# PressureSwitch.net
KiCad netlist of a schematic drawn in Altium Designer
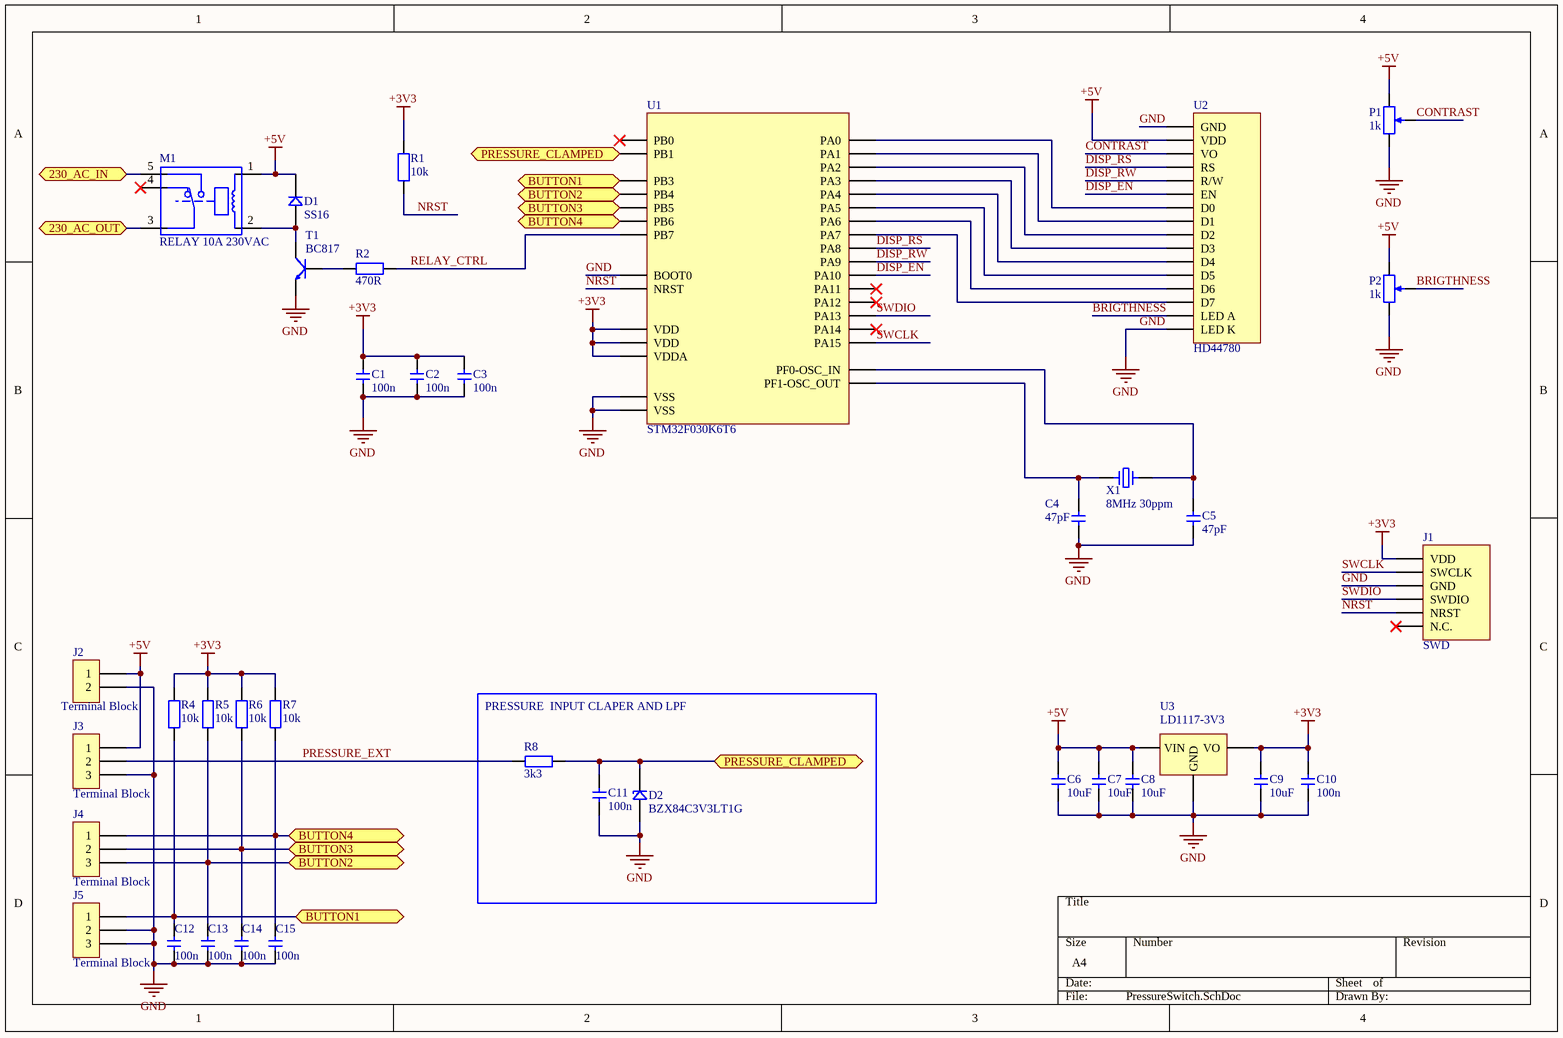
[diagram p0: PressureSwitch.SchDoc]

(export (version "E")
  (design (tool "Eeschema 10.0.6"))
  (components
    (comp (ref "C1")
      (value "100n")
      (footprint "CAP_1206")
      (description "1206  100n 50V Capacitor")
      (fields (field (name "TOLERANCE") "%") (field (name "VOLTAGE") "50V"))
      (libsource (lib "Passive") (part "100n 50V 1206"))
    )
    (comp (ref "C2")
      (value "100n")
      (footprint "CAP_1206")
      (description "1206  100n 50V Capacitor")
      (fields (field (name "TOLERANCE") "%") (field (name "VOLTAGE") "50V"))
      (libsource (lib "Passive") (part "100n 50V 1206"))
    )
    (comp (ref "C3")
      (value "100n")
      (footprint "CAP_1206")
      (description "1206  100n 50V Capacitor")
      (fields (field (name "TOLERANCE") "%") (field (name "VOLTAGE") "50V"))
      (libsource (lib "Passive") (part "100n 50V 1206"))
    )
    (comp (ref "C4")
      (value "47pF")
      (footprint "CAP_1206")
      (description "1206  47pF 50V Capacitor")
      (fields (field (name "TOLERANCE") "%") (field (name "VOLTAGE") "50V"))
      (libsource (lib "Passive") (part "47pF 50V 1206_1"))
    )
    (comp (ref "C5")
      (value "47pF")
      (footprint "CAP_1206")
      (description "1206  47pF 50V Capacitor")
      (fields (field (name "TOLERANCE") "%") (field (name "VOLTAGE") "50V"))
      (libsource (lib "Passive") (part "47pF 50V 1206_1"))
    )
    (comp (ref "C6")
      (value "10uF")
      (footprint "CAP_1206")
      (description "10uF 5% Capacitor")
      (fields (field (name "TOLERANCE") "%") (field (name "VOLTAGE") "V"))
      (libsource (lib "Passive") (part "10uF"))
    )
    (comp (ref "C7")
      (value "10uF")
      (footprint "CAP_1206")
      (description "10uF 5% Capacitor")
      (fields (field (name "TOLERANCE") "%") (field (name "VOLTAGE") "V"))
      (libsource (lib "Passive") (part "10uF"))
    )
    (comp (ref "C8")
      (value "10uF")
      (footprint "CAP_1206")
      (description "10uF 5% Capacitor")
      (fields (field (name "TOLERANCE") "%") (field (name "VOLTAGE") "V"))
      (libsource (lib "Passive") (part "10uF"))
    )
    (comp (ref "C9")
      (value "10uF")
      (footprint "CAP_1206")
      (description "10uF 5% Capacitor")
      (fields (field (name "TOLERANCE") "%") (field (name "VOLTAGE") "V"))
      (libsource (lib "Passive") (part "10uF"))
    )
    (comp (ref "C10")
      (value "100n")
      (footprint "CAP_1206")
      (description "1206  100n 50V Capacitor")
      (fields (field (name "TOLERANCE") "%") (field (name "VOLTAGE") "50V"))
      (libsource (lib "Passive") (part "100n 50V 1206"))
    )
    (comp (ref "C11")
      (value "100n")
      (footprint "CAP_1206")
      (description "1206  100n 50V Capacitor")
      (fields (field (name "TOLERANCE") "%") (field (name "VOLTAGE") "50V"))
      (libsource (lib "Passive") (part "100n 50V 1206"))
    )
    (comp (ref "C12")
      (value "100n")
      (footprint "CAP_1206")
      (description "1206  100n 50V Capacitor")
      (fields (field (name "TOLERANCE") "%") (field (name "VOLTAGE") "50V"))
      (libsource (lib "Passive") (part "100n 50V 1206"))
    )
    (comp (ref "C13")
      (value "100n")
      (footprint "CAP_1206")
      (description "1206  100n 50V Capacitor")
      (fields (field (name "TOLERANCE") "%") (field (name "VOLTAGE") "50V"))
      (libsource (lib "Passive") (part "100n 50V 1206"))
    )
    (comp (ref "C14")
      (value "100n")
      (footprint "CAP_1206")
      (description "1206  100n 50V Capacitor")
      (fields (field (name "TOLERANCE") "%") (field (name "VOLTAGE") "50V"))
      (libsource (lib "Passive") (part "100n 50V 1206"))
    )
    (comp (ref "C15")
      (value "100n")
      (footprint "CAP_1206")
      (description "1206  100n 50V Capacitor")
      (fields (field (name "TOLERANCE") "%") (field (name "VOLTAGE") "50V"))
      (libsource (lib "Passive") (part "100n 50V 1206"))
    )
    (comp (ref "D1")
      (value "SS16")
      (footprint "DO-214AC")
      (description "RECTIFIER 1A 60V")
      (libsource (lib "Discrete") (part "SS16"))
    )
    (comp (ref "D2")
      (value "BZX84C3V3LT1G")
      (footprint "SOT23-3")
      (description "3V3 ZENER DIODE 225 mW SOT−23")
      (libsource (lib "Discrete") (part "BZX84C3V3LT1G"))
    )
    (comp (ref "J1")
      (value "SWD")
      (footprint "PIN_HEADER_6P")
      (description "STM32 SWD CONNECTOR")
      (libsource (lib "Passive") (part "SWD"))
    )
    (comp (ref "J2")
      (value "Terminal Block")
      (footprint "TERMINAL_BLOCK_2P")
      (description "5.08mm Terminal Blocks 2P")
      (libsource (lib "Passive") (part "Terminal Block 2P"))
    )
    (comp (ref "J3")
      (value "Terminal Block")
      (footprint "TERMINAL_BLOCK_3P")
      (description "5.08mm Terminal Blocks 3P")
      (libsource (lib "Passive") (part "Terminal Block 3P"))
    )
    (comp (ref "J4")
      (value "Terminal Block")
      (footprint "TERMINAL_BLOCK_3P")
      (description "5.08mm Terminal Blocks 3P")
      (libsource (lib "Passive") (part "Terminal Block 3P"))
    )
    (comp (ref "J5")
      (value "Terminal Block")
      (footprint "TERMINAL_BLOCK_3P")
      (description "5.08mm Terminal Blocks 3P")
      (libsource (lib "Passive") (part "Terminal Block 3P"))
    )
    (comp (ref "M1")
      (value "RELAY 10A 230VAC")
      (footprint "Relay_10A")
      (description "MECH 5V 1xMORSE 10A/250AC S7001E5W 5DC")
      (libsource (lib "Passive") (part "RELAY 5V 10A/230VAC G6RN"))
    )
    (comp (ref "P1")
      (value "1k")
      (footprint "SMD_TRIM_POT")
      (description "Trimmer Pot 1k")
      (fields (field (name "TOLERANCE") "5%") (field (name "POWER") "W"))
      (libsource (lib "Passive") (part "1k_TRIMPOT"))
    )
    (comp (ref "P2")
      (value "1k")
      (footprint "SMD_TRIM_POT")
      (description "Trimmer Pot 1k")
      (fields (field (name "TOLERANCE") "5%") (field (name "POWER") "W"))
      (libsource (lib "Passive") (part "1k_TRIMPOT"))
    )
    (comp (ref "R1")
      (value "10k")
      (footprint "RES_1206")
      (description "1206 10k 5% Resistor")
      (fields (field (name "TOLERANCE") "5%") (field (name "POWER") "0.025W"))
      (libsource (lib "Passive") (part "10k"))
    )
    (comp (ref "R2")
      (value "470R")
      (footprint "RES_1206")
      (description "1206  470R 5% Resistor")
      (fields (field (name "TOLERANCE") "5%") (field (name "POWER") "W"))
      (libsource (lib "Passive") (part "470R"))
    )
    (comp (ref "R4")
      (value "10k")
      (footprint "RES_1206")
      (description "1206 10k 5% Resistor")
      (fields (field (name "TOLERANCE") "5%") (field (name "POWER") "0.025W"))
      (libsource (lib "Passive") (part "10k"))
    )
    (comp (ref "R5")
      (value "10k")
      (footprint "RES_1206")
      (description "1206 10k 5% Resistor")
      (fields (field (name "TOLERANCE") "5%") (field (name "POWER") "0.025W"))
      (libsource (lib "Passive") (part "10k"))
    )
    (comp (ref "R6")
      (value "10k")
      (footprint "RES_1206")
      (description "1206 10k 5% Resistor")
      (fields (field (name "TOLERANCE") "5%") (field (name "POWER") "0.025W"))
      (libsource (lib "Passive") (part "10k"))
    )
    (comp (ref "R7")
      (value "10k")
      (footprint "RES_1206")
      (description "1206 10k 5% Resistor")
      (fields (field (name "TOLERANCE") "5%") (field (name "POWER") "0.025W"))
      (libsource (lib "Passive") (part "10k"))
    )
    (comp (ref "R8")
      (value "3k3")
      (footprint "RES_1206")
      (description "1206  3k3 5% Resistor")
      (fields (field (name "TOLERANCE") "5%") (field (name "POWER") "W"))
      (libsource (lib "Passive") (part "3k3"))
    )
    (comp (ref "T1")
      (value "BC817")
      (footprint "SOT23-3")
      (description "BC817 NPN-UNI 45V 0.5A 0.25W 200MHz SOT-23")
      (fields (field (name "POWER") "0.25W"))
      (libsource (lib "Discrete") (part "BC817"))
    )
    (comp (ref "U1")
      (value "STM32F030K6T6")
      (footprint "LQFP32")
      (description "Value-line ARM 32bit MCU with 32k Flash")
      (libsource (lib "IC") (part "STM32F030K6T6"))
    )
    (comp (ref "U2")
      (value "HD44780")
      (footprint "SOCKET_HEADER_16P")
      (description "16x2 CHARACTER DISPLAY")
      (libsource (lib "IC") (part "HD44780"))
    )
    (comp (ref "U3")
      (value "LD1117-3V3")
      (footprint "SOT223-3")
      (description "3.3V low drop positive voltage regulator")
      (libsource (lib "IC") (part "LD1117-3V3"))
    )
    (comp (ref "X1")
      (value "8MHz 30ppm")
      (footprint "HC49")
      (description "8.000MHz QUARZ HC49 30ppm 20pF LOW PROFILE")
      (libsource (lib "Passive") (part "XTAL_8MHZ"))
    )
  )
  (nets
    (net (code "1") (name "+3V3") (class "Default")
      (node (ref "C1") (pin "2") (pinfunction "2_2") (pintype "passive"))
      (node (ref "C10") (pin "2") (pinfunction "2_2") (pintype "passive"))
      (node (ref "C2") (pin "2") (pinfunction "2_2") (pintype "passive"))
      (node (ref "C3") (pin "2") (pinfunction "2_2") (pintype "passive"))
      (node (ref "C9") (pin "2") (pinfunction "2_2") (pintype "passive"))
      (node (ref "J1") (pin "1") (pinfunction "VDD_1") (pintype "passive"))
      (node (ref "R1") (pin "2") (pinfunction "2_2") (pintype "passive"))
      (node (ref "R4") (pin "2") (pinfunction "2_2") (pintype "passive"))
      (node (ref "R5") (pin "2") (pinfunction "2_2") (pintype "passive"))
      (node (ref "R6") (pin "2") (pinfunction "2_2") (pintype "passive"))
      (node (ref "R7") (pin "2") (pinfunction "2_2") (pintype "passive"))
      (node (ref "U1") (pin "1") (pinfunction "VDD_1") (pintype "passive"))
      (node (ref "U1") (pin "17") (pinfunction "VDD_17") (pintype "passive"))
      (node (ref "U1") (pin "5") (pinfunction "VDDA_5") (pintype "passive"))
      (node (ref "U3") (pin "2") (pinfunction "VO_2") (pintype "passive"))
    )
    (net (code "2") (name "+5V") (class "Default")
      (node (ref "C6") (pin "2") (pinfunction "2_2") (pintype "passive"))
      (node (ref "C7") (pin "2") (pinfunction "2_2") (pintype "passive"))
      (node (ref "C8") (pin "2") (pinfunction "2_2") (pintype "passive"))
      (node (ref "D1") (pin "2") (pinfunction "2_2") (pintype "passive"))
      (node (ref "J2") (pin "1") (pinfunction "1_1") (pintype "passive"))
      (node (ref "J3") (pin "1") (pinfunction "1_1") (pintype "passive"))
      (node (ref "M1") (pin "1") (pinfunction "1_1") (pintype "passive"))
      (node (ref "P1") (pin "1") (pinfunction "1_1") (pintype "passive"))
      (node (ref "P2") (pin "1") (pinfunction "1_1") (pintype "passive"))
      (node (ref "U2") (pin "2") (pinfunction "VDD_2") (pintype "passive"))
      (node (ref "U3") (pin "3") (pinfunction "VIN_3") (pintype "passive"))
    )
    (net (code "3") (name "/230_AC_IN") (class "Default")
      (node (ref "M1") (pin "5") (pinfunction "5_5") (pintype "passive"))
    )
    (net (code "4") (name "/230_AC_OUT") (class "Default")
      (node (ref "M1") (pin "3") (pinfunction "3_3") (pintype "passive"))
    )
    (net (code "5") (name "/BRIGTHNESS") (class "Default")
      (node (ref "P2") (pin "3") (pinfunction "3_3") (pintype "passive"))
      (node (ref "U2") (pin "15") (pinfunction "LED_A_15") (pintype "passive"))
    )
    (net (code "6") (name "/BUTTON1") (class "Default")
      (node (ref "C12") (pin "2") (pinfunction "2_2") (pintype "passive"))
      (node (ref "J5") (pin "1") (pinfunction "1_1") (pintype "passive"))
      (node (ref "R4") (pin "1") (pinfunction "1_1") (pintype "passive"))
      (node (ref "U1") (pin "26") (pinfunction "PB3_26") (pintype "passive"))
    )
    (net (code "7") (name "/BUTTON2") (class "Default")
      (node (ref "C13") (pin "2") (pinfunction "2_2") (pintype "passive"))
      (node (ref "J4") (pin "3") (pinfunction "3_3") (pintype "passive"))
      (node (ref "R5") (pin "1") (pinfunction "1_1") (pintype "passive"))
      (node (ref "U1") (pin "27") (pinfunction "PB4_27") (pintype "passive"))
    )
    (net (code "8") (name "/BUTTON3") (class "Default")
      (node (ref "C14") (pin "2") (pinfunction "2_2") (pintype "passive"))
      (node (ref "J4") (pin "2") (pinfunction "2_2") (pintype "passive"))
      (node (ref "R6") (pin "1") (pinfunction "1_1") (pintype "passive"))
      (node (ref "U1") (pin "28") (pinfunction "PB5_28") (pintype "passive"))
    )
    (net (code "9") (name "/BUTTON4") (class "Default")
      (node (ref "C15") (pin "2") (pinfunction "2_2") (pintype "passive"))
      (node (ref "J4") (pin "1") (pinfunction "1_1") (pintype "passive"))
      (node (ref "R7") (pin "1") (pinfunction "1_1") (pintype "passive"))
      (node (ref "U1") (pin "29") (pinfunction "PB6_29") (pintype "passive"))
    )
    (net (code "10") (name "/CONTRAST") (class "Default")
      (node (ref "P1") (pin "3") (pinfunction "3_3") (pintype "passive"))
      (node (ref "U2") (pin "3") (pinfunction "VO_3") (pintype "passive"))
    )
    (net (code "11") (name "/DISP_EN") (class "Default")
      (node (ref "U1") (pin "20") (pinfunction "PA10_20") (pintype "passive"))
      (node (ref "U2") (pin "6") (pinfunction "EN_6") (pintype "passive"))
    )
    (net (code "12") (name "/DISP_RS") (class "Default")
      (node (ref "U1") (pin "18") (pinfunction "PA8_18") (pintype "passive"))
      (node (ref "U2") (pin "4") (pinfunction "RS_4") (pintype "passive"))
    )
    (net (code "13") (name "/DISP_RW") (class "Default")
      (node (ref "U1") (pin "19") (pinfunction "PA9_19") (pintype "passive"))
      (node (ref "U2") (pin "5") (pinfunction "R/W_5") (pintype "passive"))
    )
    (net (code "14") (name "/NRST") (class "Default")
      (node (ref "J1") (pin "5") (pinfunction "NRST_5") (pintype "passive"))
      (node (ref "R1") (pin "1") (pinfunction "1_1") (pintype "passive"))
      (node (ref "U1") (pin "4") (pinfunction "NRST_4") (pintype "passive"))
    )
    (net (code "15") (name "/PRESSURE_CLAMPED") (class "Default")
      (node (ref "C11") (pin "2") (pinfunction "2_2") (pintype "passive"))
      (node (ref "D2") (pin "3") (pinfunction "3_3") (pintype "passive"))
      (node (ref "R8") (pin "2") (pinfunction "2_2") (pintype "passive"))
      (node (ref "U1") (pin "15") (pinfunction "PB1_15") (pintype "passive"))
    )
    (net (code "16") (name "/PRESSURE_EXT") (class "Default")
      (node (ref "J3") (pin "2") (pinfunction "2_2") (pintype "passive"))
      (node (ref "R8") (pin "1") (pinfunction "1_1") (pintype "passive"))
    )
    (net (code "17") (name "/RELAY_CTRL") (class "Default")
      (node (ref "R2") (pin "2") (pinfunction "2_2") (pintype "passive"))
      (node (ref "U1") (pin "30") (pinfunction "PB7_30") (pintype "passive"))
    )
    (net (code "18") (name "/SWCLK") (class "Default")
      (node (ref "J1") (pin "2") (pinfunction "SWCLK_2") (pintype "passive"))
      (node (ref "U1") (pin "25") (pinfunction "PA15_25") (pintype "passive"))
    )
    (net (code "19") (name "/SWDIO") (class "Default")
      (node (ref "J1") (pin "4") (pinfunction "SWDIO_4") (pintype "passive"))
      (node (ref "U1") (pin "23") (pinfunction "PA13_23") (pintype "passive"))
    )
    (net (code "20") (name "GND") (class "Default")
      (node (ref "C1") (pin "1") (pinfunction "1_1") (pintype "passive"))
      (node (ref "C10") (pin "1") (pinfunction "1_1") (pintype "passive"))
      (node (ref "C11") (pin "1") (pinfunction "1_1") (pintype "passive"))
      (node (ref "C12") (pin "1") (pinfunction "1_1") (pintype "passive"))
      (node (ref "C13") (pin "1") (pinfunction "1_1") (pintype "passive"))
      (node (ref "C14") (pin "1") (pinfunction "1_1") (pintype "passive"))
      (node (ref "C15") (pin "1") (pinfunction "1_1") (pintype "passive"))
      (node (ref "C2") (pin "1") (pinfunction "1_1") (pintype "passive"))
      (node (ref "C3") (pin "1") (pinfunction "1_1") (pintype "passive"))
      (node (ref "C4") (pin "1") (pinfunction "1_1") (pintype "passive"))
      (node (ref "C5") (pin "1") (pinfunction "1_1") (pintype "passive"))
      (node (ref "C6") (pin "1") (pinfunction "1_1") (pintype "passive"))
      (node (ref "C7") (pin "1") (pinfunction "1_1") (pintype "passive"))
      (node (ref "C8") (pin "1") (pinfunction "1_1") (pintype "passive"))
      (node (ref "C9") (pin "1") (pinfunction "1_1") (pintype "passive"))
      (node (ref "D2") (pin "1") (pinfunction "1_1") (pintype "passive"))
      (node (ref "J1") (pin "3") (pinfunction "GND_3") (pintype "passive"))
      (node (ref "J2") (pin "2") (pinfunction "2_2") (pintype "passive"))
      (node (ref "J3") (pin "3") (pinfunction "3_3") (pintype "passive"))
      (node (ref "J5") (pin "2") (pinfunction "2_2") (pintype "passive"))
      (node (ref "J5") (pin "3") (pinfunction "3_3") (pintype "passive"))
      (node (ref "P1") (pin "2") (pinfunction "2_2") (pintype "passive"))
      (node (ref "P2") (pin "2") (pinfunction "2_2") (pintype "passive"))
      (node (ref "T1") (pin "2") (pinfunction "E_2") (pintype "passive"))
      (node (ref "U1") (pin "16") (pinfunction "VSS_16") (pintype "passive"))
      (node (ref "U1") (pin "31") (pinfunction "BOOT0_31") (pintype "passive"))
      (node (ref "U1") (pin "32") (pinfunction "VSS_32") (pintype "passive"))
      (node (ref "U2") (pin "1") (pinfunction "GND_1") (pintype "passive"))
      (node (ref "U2") (pin "16") (pinfunction "LED_K_16") (pintype "passive"))
      (node (ref "U3") (pin "1") (pinfunction "GND_1") (pintype "passive"))
    )
    (net (code "21") (name "Net-(T1-B)") (class "Default")
      (node (ref "R2") (pin "1") (pinfunction "1_1") (pintype "passive"))
      (node (ref "T1") (pin "1") (pinfunction "B_1") (pintype "passive"))
    )
    (net (code "22") (name "Net-(T1-C)") (class "Default")
      (node (ref "D1") (pin "1") (pinfunction "1_1") (pintype "passive"))
      (node (ref "M1") (pin "2") (pinfunction "2_2") (pintype "passive"))
      (node (ref "T1") (pin "3") (pinfunction "C_3") (pintype "passive"))
    )
    (net (code "23") (name "Net-(U1-PA0)") (class "Default")
      (node (ref "U1") (pin "6") (pinfunction "PA0_6") (pintype "passive"))
      (node (ref "U2") (pin "7") (pinfunction "D0_7") (pintype "passive"))
    )
    (net (code "24") (name "Net-(U1-PA1)") (class "Default")
      (node (ref "U1") (pin "7") (pinfunction "PA1_7") (pintype "passive"))
      (node (ref "U2") (pin "8") (pinfunction "D1_8") (pintype "passive"))
    )
    (net (code "25") (name "Net-(U1-PA2)") (class "Default")
      (node (ref "U1") (pin "8") (pinfunction "PA2_8") (pintype "passive"))
      (node (ref "U2") (pin "9") (pinfunction "D2_9") (pintype "passive"))
    )
    (net (code "26") (name "Net-(U1-PA3)") (class "Default")
      (node (ref "U1") (pin "9") (pinfunction "PA3_9") (pintype "passive"))
      (node (ref "U2") (pin "10") (pinfunction "D3_10") (pintype "passive"))
    )
    (net (code "27") (name "Net-(U1-PA4)") (class "Default")
      (node (ref "U1") (pin "10") (pinfunction "PA4_10") (pintype "passive"))
      (node (ref "U2") (pin "11") (pinfunction "D4_11") (pintype "passive"))
    )
    (net (code "28") (name "Net-(U1-PA5)") (class "Default")
      (node (ref "U1") (pin "11") (pinfunction "PA5_11") (pintype "passive"))
      (node (ref "U2") (pin "12") (pinfunction "D5_12") (pintype "passive"))
    )
    (net (code "29") (name "Net-(U1-PA6)") (class "Default")
      (node (ref "U1") (pin "12") (pinfunction "PA6_12") (pintype "passive"))
      (node (ref "U2") (pin "13") (pinfunction "D6_13") (pintype "passive"))
    )
    (net (code "30") (name "Net-(U1-PA7)") (class "Default")
      (node (ref "U1") (pin "13") (pinfunction "PA7_13") (pintype "passive"))
      (node (ref "U2") (pin "14") (pinfunction "D7_14") (pintype "passive"))
    )
    (net (code "31") (name "Net-(U1-PF0-OSC_IN)") (class "Default")
      (node (ref "C5") (pin "2") (pinfunction "2_2") (pintype "passive"))
      (node (ref "U1") (pin "2") (pinfunction "PF0-OSC_IN_2") (pintype "passive"))
      (node (ref "X1") (pin "1") (pinfunction "1_1") (pintype "passive"))
    )
    (net (code "32") (name "Net-(U1-PF1-OSC_OUT)") (class "Default")
      (node (ref "C4") (pin "2") (pinfunction "2_2") (pintype "passive"))
      (node (ref "U1") (pin "3") (pinfunction "PF1-OSC_OUT_3") (pintype "passive"))
      (node (ref "X1") (pin "2") (pinfunction "2_2") (pintype "passive"))
    )
    (net (code "33") (name "unconnected-(J1-N.C.-Pad6)") (class "Default")
      (node (ref "J1") (pin "6") (pinfunction "N.C._6") (pintype "passive+no_connect"))
    )
    (net (code "34") (name "unconnected-(M1-Pad4)") (class "Default")
      (node (ref "M1") (pin "4") (pinfunction "4_4") (pintype "passive+no_connect"))
    )
    (net (code "35") (name "unconnected-(U1-PA11-Pad21)") (class "Default")
      (node (ref "U1") (pin "21") (pinfunction "PA11_21") (pintype "passive+no_connect"))
    )
    (net (code "36") (name "unconnected-(U1-PA12-Pad22)") (class "Default")
      (node (ref "U1") (pin "22") (pinfunction "PA12_22") (pintype "passive+no_connect"))
    )
    (net (code "37") (name "unconnected-(U1-PA14-Pad24)") (class "Default")
      (node (ref "U1") (pin "24") (pinfunction "PA14_24") (pintype "passive+no_connect"))
    )
    (net (code "38") (name "unconnected-(U1-PB0-Pad14)") (class "Default")
      (node (ref "U1") (pin "14") (pinfunction "PB0_14") (pintype "passive+no_connect"))
    )
  )
)
